# 1_ADSTM32-Power.net
KiCad netlist of a schematic drawn in Altium Designer
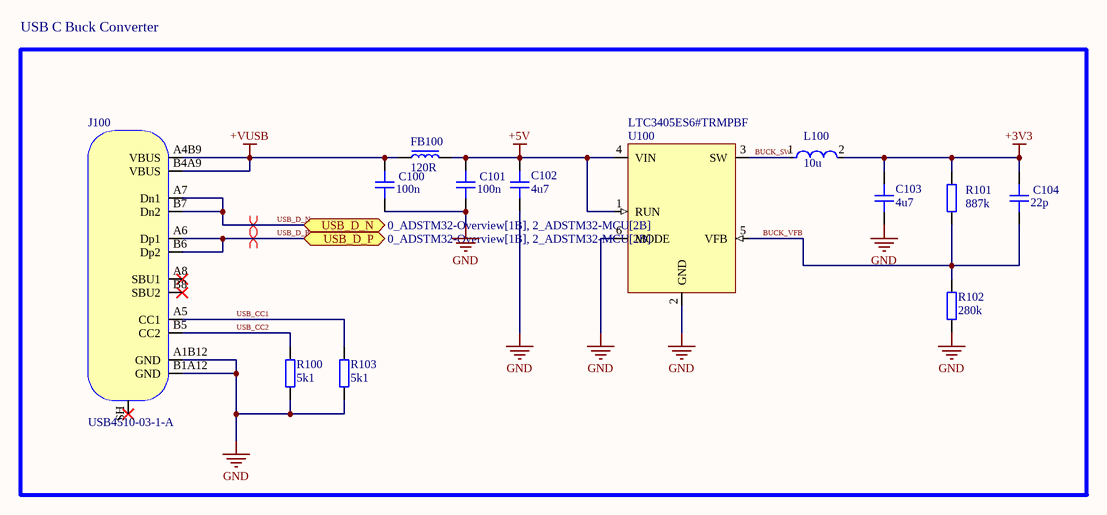
[diagram p0: 1_ADSTM32-Power.SchDoc]

(export (version "E")
  (design (tool "Eeschema 10.0.6"))
  (components
    (comp (ref "C100")
      (value "100n")
      (footprint "CAP_0603")
      (description "Capacitor SMD 0603 16V")
      (libsource (lib "Schematic-Lib-PhilsLab") (part "CAP_0603_16V"))
    )
    (comp (ref "C101")
      (value "100n")
      (footprint "CAP_0603")
      (description "Capacitor SMD 0603 16V")
      (libsource (lib "Schematic-Lib-PhilsLab") (part "CAP_0603_16V"))
    )
    (comp (ref "C102")
      (value "4u7")
      (footprint "CAP_0805")
      (description "Capacitor SMD 0805 16V")
      (libsource (lib "Schematic-Lib-PhilsLab") (part "CAP_0805_16V"))
    )
    (comp (ref "C103")
      (value "4u7")
      (footprint "CAP_0805")
      (description "Capacitor SMD 0805 16V")
      (libsource (lib "Schematic-Lib-PhilsLab") (part "CAP_0805_16V"))
    )
    (comp (ref "C104")
      (value "22p")
      (footprint "CAP_0603")
      (description "Capacitor SMD 0603 16V")
      (libsource (lib "Schematic-Lib-PhilsLab") (part "CAP_0603_16V"))
    )
    (comp (ref "FB100")
      (value "120R")
      (footprint "FB_0603")
      (description "Ferrite Bead SMD 0603")
      (libsource (lib "Schematic-Lib-PhilsLab") (part "FB_0603"))
    )
    (comp (ref "J100")
      (value "USB4510-03-1-A")
      (footprint "USB4510-03-1-A")
      (description "USB Connector Type C SMT Mid-Mount 16 Pin")
      (fields (field (name "MANUFACTURER") "GCT"))
      (libsource (lib "Schematic-Lib-PhilsLab") (part "USB4510-03-1-A"))
    )
    (comp (ref "L100")
      (value "10u")
      (footprint "FP-NRH2412-MFG")
      (description "Shielded Wirewound Inductor 10uH 20% 0.51A 0.72Ω SMD")
      (fields (field (name "TOLERANCE") "20%"))
      (libsource (lib "Altium Content Vault") (part "725321dda6339637d4d059423bc1c3c"))
    )
    (comp (ref "R100")
      (value "5k1")
      (footprint "RES_0603")
      (description "Resistor SMD 0603")
      (libsource (lib "Schematic-Lib-PhilsLab") (part "RES_0603"))
    )
    (comp (ref "R101")
      (value "887k")
      (footprint "RES_0603")
      (description "Resistor SMD 0603")
      (libsource (lib "Schematic-Lib-PhilsLab") (part "RES_0603"))
    )
    (comp (ref "R102")
      (value "280k")
      (footprint "RES_0603")
      (description "Resistor SMD 0603")
      (libsource (lib "Schematic-Lib-PhilsLab") (part "RES_0603"))
    )
    (comp (ref "R103")
      (value "5k1")
      (footprint "RES_0603")
      (description "Resistor SMD 0603")
      (libsource (lib "Schematic-Lib-PhilsLab") (part "RES_0603"))
    )
    (comp (ref "U100")
      (value "LTC3405ES6#TRMPBF")
      (footprint "SOT-23-6")
      (description "1.5MHz, 300mA\r\nSynchronous Step-Down\r\nRegulator in ThinSOT")
      (fields (field (name "MANUFACTURER") "Analog Devices"))
      (libsource (lib "Schematic-Lib-PhilsLab") (part "LTC3405ES6#TRMPBF"))
    )
  )
  (nets
    (net (code "1") (name "+3V3") (class "Default")
      (node (ref "C103") (pin "2") (pinfunction "2_2") (pintype "passive"))
      (node (ref "C104") (pin "2") (pinfunction "2_2") (pintype "passive"))
      (node (ref "L100") (pin "2") (pinfunction "2_2") (pintype "passive"))
      (node (ref "R101") (pin "2") (pinfunction "2_2") (pintype "passive"))
    )
    (net (code "2") (name "+5V") (class "Default")
      (node (ref "C101") (pin "2") (pinfunction "2_2") (pintype "passive"))
      (node (ref "C102") (pin "2") (pinfunction "2_2") (pintype "passive"))
      (node (ref "FB100") (pin "2") (pinfunction "2_2") (pintype "passive"))
      (node (ref "U100") (pin "1") (pinfunction "RUN_1") (pintype "input"))
      (node (ref "U100") (pin "4") (pinfunction "VIN_4") (pintype "power_in"))
    )
    (net (code "3") (name "+VUSB") (class "Default")
      (node (ref "C100") (pin "2") (pinfunction "2_2") (pintype "passive"))
      (node (ref "FB100") (pin "1") (pinfunction "1_1") (pintype "passive"))
      (node (ref "J100") (pin "A4B9") (pinfunction "VBUS_A4B9") (pintype "passive"))
      (node (ref "J100") (pin "B4A9") (pinfunction "VBUS_B4A9") (pintype "passive"))
    )
    (net (code "4") (name "/BUCK_SW") (class "Default")
      (node (ref "L100") (pin "1") (pinfunction "1_1") (pintype "passive"))
      (node (ref "U100") (pin "3") (pinfunction "SW_3") (pintype "power_in"))
    )
    (net (code "5") (name "/BUCK_VFB") (class "Default")
      (node (ref "C104") (pin "1") (pinfunction "1_1") (pintype "passive"))
      (node (ref "R101") (pin "1") (pinfunction "1_1") (pintype "passive"))
      (node (ref "R102") (pin "2") (pinfunction "2_2") (pintype "passive"))
      (node (ref "U100") (pin "5") (pinfunction "VFB_5") (pintype "input"))
    )
    (net (code "6") (name "/USB_CC1") (class "Default")
      (node (ref "J100") (pin "A5") (pinfunction "CC1_A5") (pintype "passive"))
      (node (ref "R103") (pin "2") (pinfunction "2_2") (pintype "passive"))
    )
    (net (code "7") (name "/USB_CC2") (class "Default")
      (node (ref "J100") (pin "B5") (pinfunction "CC2_B5") (pintype "passive"))
      (node (ref "R100") (pin "2") (pinfunction "2_2") (pintype "passive"))
    )
    (net (code "8") (name "/USB_D_N") (class "Default")
      (node (ref "J100") (pin "A7") (pinfunction "Dn1_A7") (pintype "passive"))
      (node (ref "J100") (pin "B7") (pinfunction "Dn2_B7") (pintype "passive"))
    )
    (net (code "9") (name "/USB_D_P") (class "Default")
      (node (ref "J100") (pin "A6") (pinfunction "Dp1_A6") (pintype "passive"))
      (node (ref "J100") (pin "B6") (pinfunction "Dp2_B6") (pintype "passive"))
    )
    (net (code "10") (name "GND") (class "Default")
      (node (ref "C100") (pin "1") (pinfunction "1_1") (pintype "passive"))
      (node (ref "C101") (pin "1") (pinfunction "1_1") (pintype "passive"))
      (node (ref "C102") (pin "1") (pinfunction "1_1") (pintype "passive"))
      (node (ref "C103") (pin "1") (pinfunction "1_1") (pintype "passive"))
      (node (ref "J100") (pin "A1B12") (pinfunction "GND_A1B12") (pintype "passive"))
      (node (ref "J100") (pin "B1A12") (pinfunction "GND_B1A12") (pintype "passive"))
      (node (ref "R100") (pin "1") (pinfunction "1_1") (pintype "passive"))
      (node (ref "R102") (pin "1") (pinfunction "1_1") (pintype "passive"))
      (node (ref "R103") (pin "1") (pinfunction "1_1") (pintype "passive"))
      (node (ref "U100") (pin "2") (pinfunction "GND_2") (pintype "power_in"))
      (node (ref "U100") (pin "6") (pinfunction "MODE_6") (pintype "passive"))
    )
    (net (code "11") (name "unconnected-(J100-SBU1-PadA8)") (class "Default")
      (node (ref "J100") (pin "A8") (pinfunction "SBU1_A8") (pintype "passive+no_connect"))
    )
    (net (code "12") (name "unconnected-(J100-SBU2-PadB8)") (class "Default")
      (node (ref "J100") (pin "B8") (pinfunction "SBU2_B8") (pintype "passive+no_connect"))
    )
    (net (code "13") (name "unconnected-(J100-SHIELD-PadSH)") (class "Default")
      (node (ref "J100") (pin "SH") (pinfunction "SHIELD_SH") (pintype "passive+no_connect"))
    )
  )
)
